# STM32-Nucleo-144_U575ZI-Q.net
KiCad netlist of a schematic drawn in Altium Designer
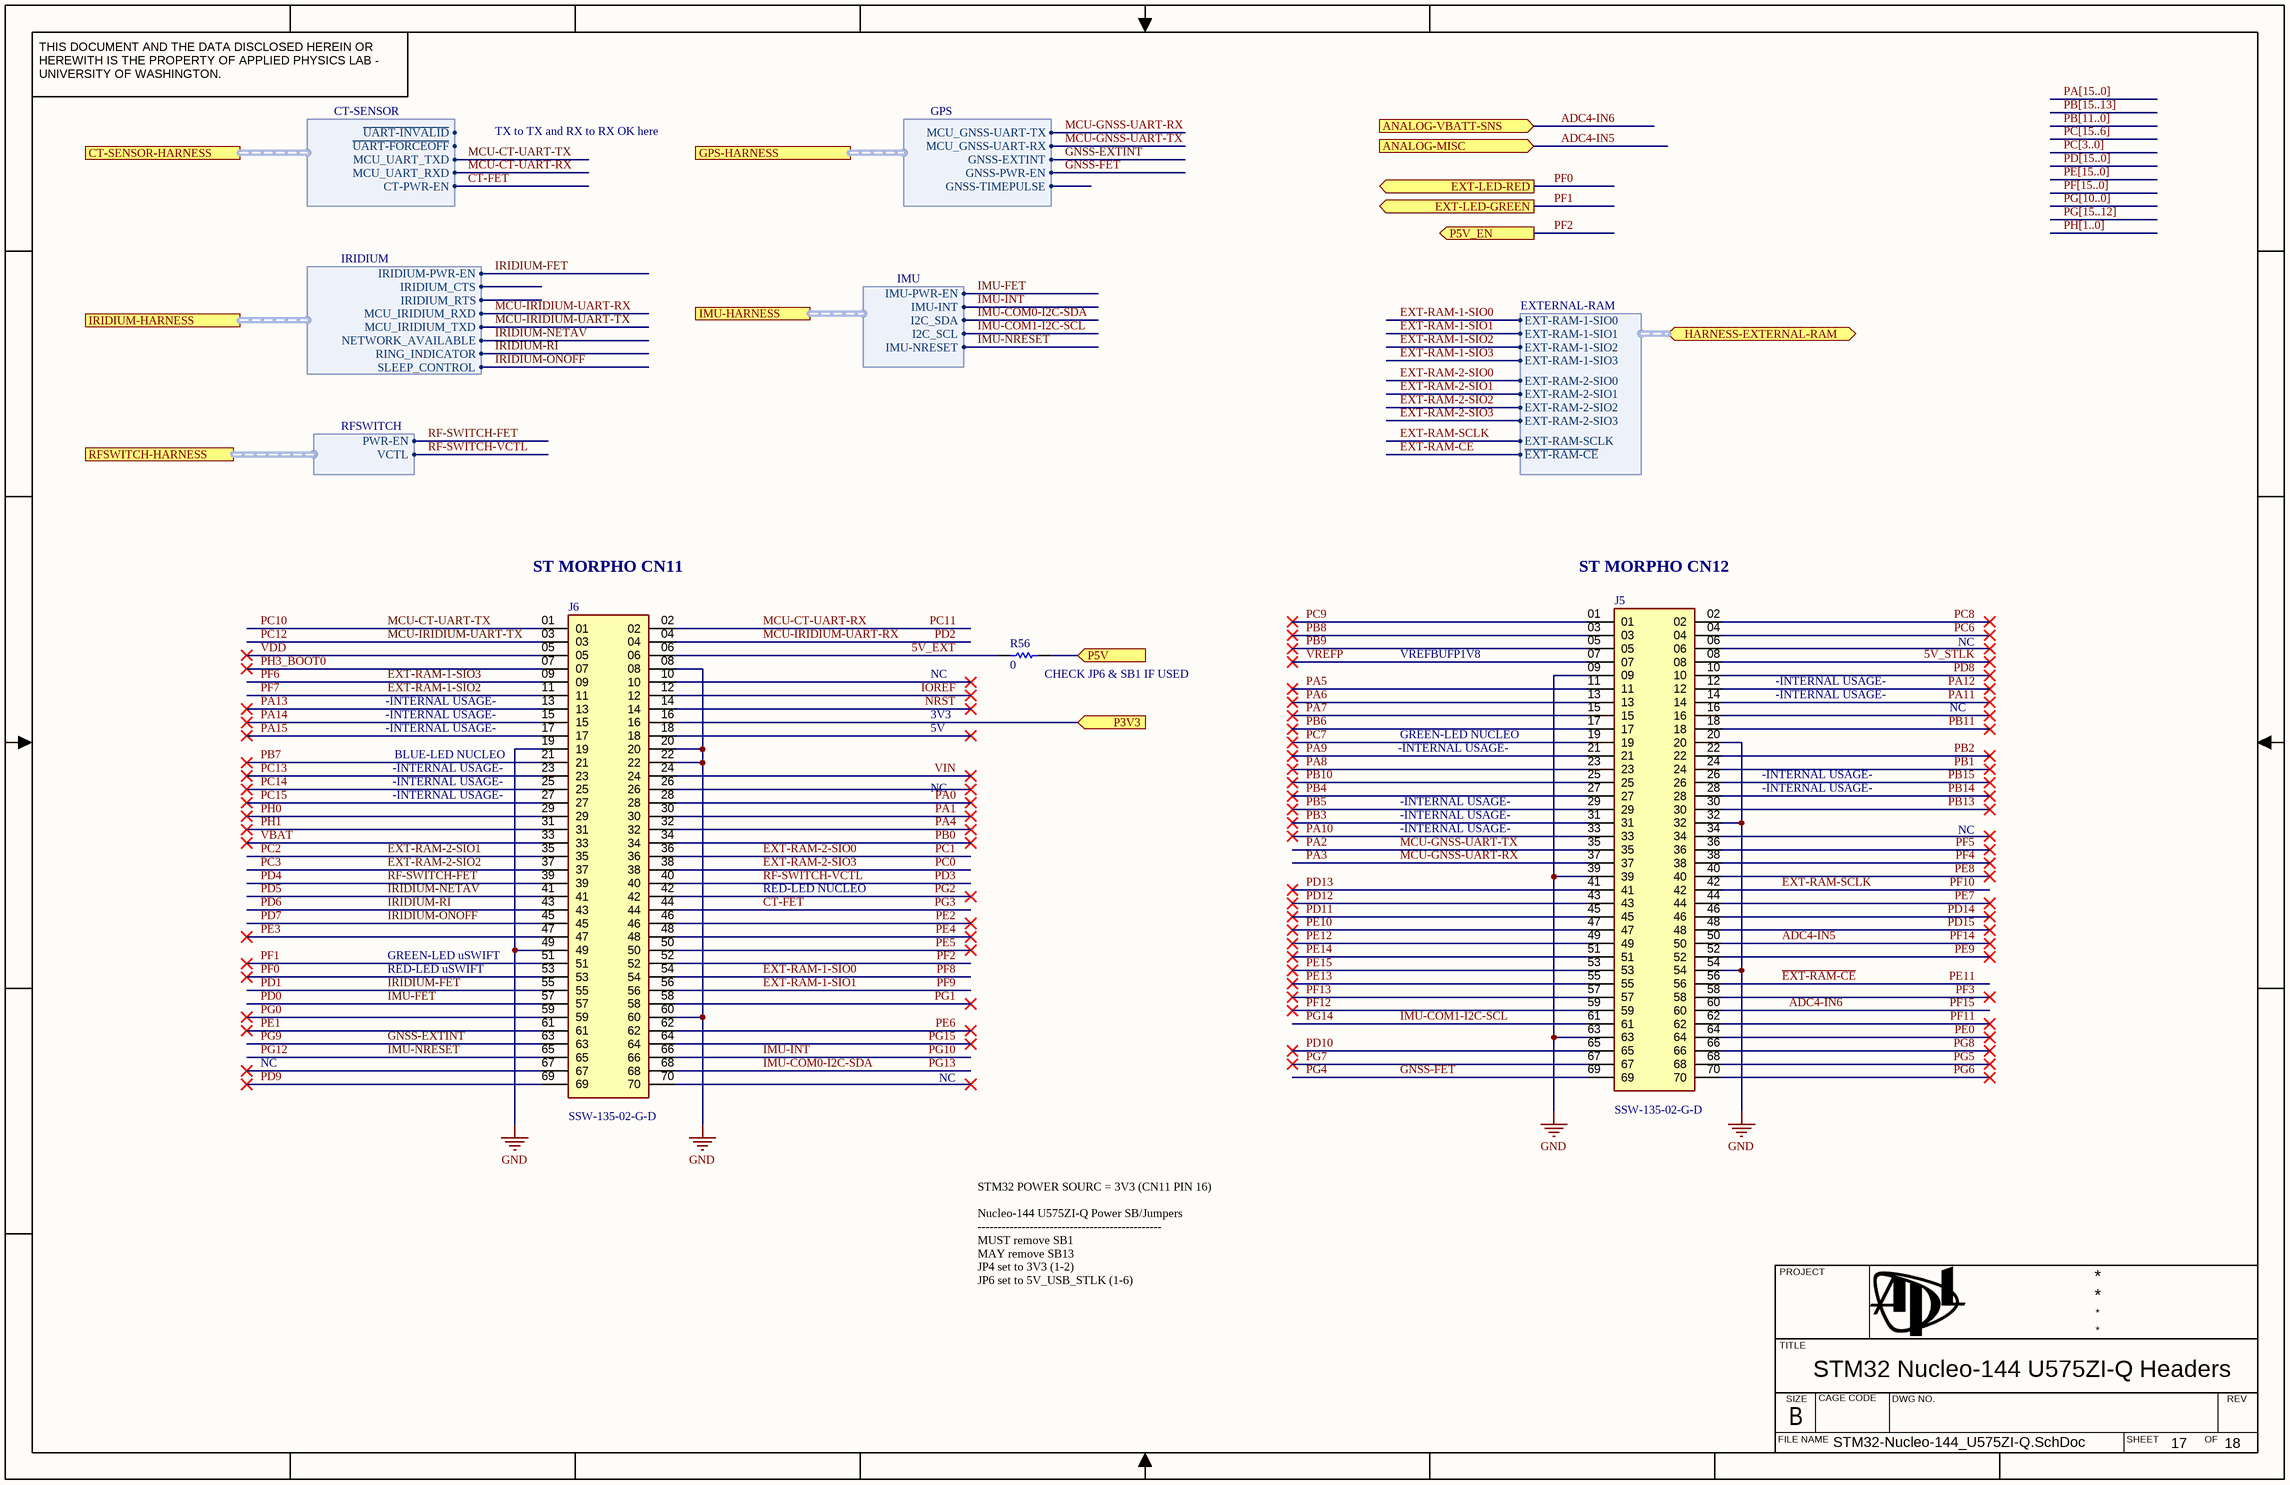
[diagram p0: STM32-Nucleo-144_U575ZI-Q.SchDoc]

(export (version "E")
  (design (tool "Eeschema 10.0.6"))
  (components
    (comp (ref "J5")
      (value "SSW-135-02-G-D")
      (footprint "SAMTEC_SSW-135-02-G-D")
      (description "Tiger Buy™ Socket Strip with PCB Tails, 0.100\" Pitch")
      (fields (field (name "MANUFACTURER") "Samtec"))
      (libsource (lib "Applied Physics Lab") (part "SSW-135-02-G-D"))
    )
    (comp (ref "J6")
      (value "SSW-135-02-G-D")
      (footprint "SAMTEC_SSW-135-02-G-D")
      (description "Tiger Buy™ Socket Strip with PCB Tails, 0.100\" Pitch")
      (fields (field (name "MANUFACTURER") "Samtec"))
      (libsource (lib "Applied Physics Lab") (part "SSW-135-02-G-D"))
    )
    (comp (ref "R56")
      (value "0")
      (footprint "RESC2013X50X35ML15T15")
      (description "Chip Resistor, 0 Ohm, +/- 1%, 125 mW, -55 to 155 degC, 0805 (2012 Metric)")
      (fields (field (name "TOLERANCE") "1%") (field (name "POWER") "125mW"))
      (libsource (lib "Applied Physics Lab") (part "RES-2"))
    )
  )
  (nets
    (net (code "7") (name "/5V_EXT") (class "Default")
      (node (ref "J6") (pin "06") (pinfunction "06_06") (pintype "passive"))
      (node (ref "R56") (pin "2") (pinfunction "2_2") (pintype "passive"))
    )
    (net (code "8") (name "/5V_STLK") (class "Default")
      (node (ref "J5") (pin "08") (pinfunction "08_08") (pintype "passive+no_connect"))
    )
    (net (code "9") (name "/IOREF") (class "Default")
      (node (ref "J6") (pin "12") (pinfunction "12_12") (pintype "passive+no_connect"))
    )
    (net (code "10") (name "/NRST") (class "Default")
      (node (ref "J6") (pin "14") (pinfunction "14_14") (pintype "passive+no_connect"))
    )
    (net (code "11") (name "/P3V3") (class "Default")
      (node (ref "J6") (pin "16") (pinfunction "16_16") (pintype "passive"))
    )
    (net (code "12") (name "/P5V") (class "Default")
      (node (ref "R56") (pin "1") (pinfunction "1_1") (pintype "passive"))
    )
    (net (code "13") (name "/PA0") (class "Default")
      (node (ref "J6") (pin "28") (pinfunction "28_28") (pintype "passive+no_connect"))
    )
    (net (code "14") (name "/PA1") (class "Default")
      (node (ref "J6") (pin "30") (pinfunction "30_30") (pintype "passive+no_connect"))
    )
    (net (code "15") (name "/PA2") (class "Default")
      (node (ref "J5") (pin "35") (pinfunction "35_35") (pintype "passive"))
    )
    (net (code "16") (name "/PA3") (class "Default")
      (node (ref "J5") (pin "37") (pinfunction "37_37") (pintype "passive"))
    )
    (net (code "17") (name "/PA4") (class "Default")
      (node (ref "J6") (pin "32") (pinfunction "32_32") (pintype "passive+no_connect"))
    )
    (net (code "18") (name "/PA5") (class "Default")
      (node (ref "J5") (pin "11") (pinfunction "11_11") (pintype "passive+no_connect"))
    )
    (net (code "19") (name "/PA6") (class "Default")
      (node (ref "J5") (pin "13") (pinfunction "13_13") (pintype "passive+no_connect"))
    )
    (net (code "20") (name "/PA7") (class "Default")
      (node (ref "J5") (pin "15") (pinfunction "15_15") (pintype "passive+no_connect"))
    )
    (net (code "21") (name "/PA8") (class "Default")
      (node (ref "J5") (pin "23") (pinfunction "23_23") (pintype "passive+no_connect"))
    )
    (net (code "22") (name "/PA9") (class "Default")
      (node (ref "J5") (pin "21") (pinfunction "21_21") (pintype "passive+no_connect"))
    )
    (net (code "23") (name "/PA10") (class "Default")
      (node (ref "J5") (pin "33") (pinfunction "33_33") (pintype "passive+no_connect"))
    )
    (net (code "24") (name "/PA11") (class "Default")
      (node (ref "J5") (pin "14") (pinfunction "14_14") (pintype "passive+no_connect"))
    )
    (net (code "25") (name "/PA12") (class "Default")
      (node (ref "J5") (pin "12") (pinfunction "12_12") (pintype "passive+no_connect"))
    )
    (net (code "26") (name "/PA13") (class "Default")
      (node (ref "J6") (pin "13") (pinfunction "13_13") (pintype "passive+no_connect"))
    )
    (net (code "27") (name "/PA14") (class "Default")
      (node (ref "J6") (pin "15") (pinfunction "15_15") (pintype "passive+no_connect"))
    )
    (net (code "28") (name "/PA15") (class "Default")
      (node (ref "J6") (pin "17") (pinfunction "17_17") (pintype "passive+no_connect"))
    )
    (net (code "30") (name "/PB0") (class "Default")
      (node (ref "J6") (pin "34") (pinfunction "34_34") (pintype "passive+no_connect"))
    )
    (net (code "31") (name "/PB1") (class "Default")
      (node (ref "J5") (pin "24") (pinfunction "24_24") (pintype "passive+no_connect"))
    )
    (net (code "32") (name "/PB2") (class "Default")
      (node (ref "J5") (pin "22") (pinfunction "22_22") (pintype "passive+no_connect"))
    )
    (net (code "33") (name "/PB3") (class "Default")
      (node (ref "J5") (pin "31") (pinfunction "31_31") (pintype "passive+no_connect"))
    )
    (net (code "34") (name "/PB4") (class "Default")
      (node (ref "J5") (pin "27") (pinfunction "27_27") (pintype "passive+no_connect"))
    )
    (net (code "35") (name "/PB5") (class "Default")
      (node (ref "J5") (pin "29") (pinfunction "29_29") (pintype "passive+no_connect"))
    )
    (net (code "36") (name "/PB6") (class "Default")
      (node (ref "J5") (pin "17") (pinfunction "17_17") (pintype "passive+no_connect"))
    )
    (net (code "37") (name "/PB7") (class "Default")
      (node (ref "J6") (pin "21") (pinfunction "21_21") (pintype "passive+no_connect"))
    )
    (net (code "38") (name "/PB8") (class "Default")
      (node (ref "J5") (pin "03") (pinfunction "03_03") (pintype "passive+no_connect"))
    )
    (net (code "39") (name "/PB9") (class "Default")
      (node (ref "J5") (pin "05") (pinfunction "05_05") (pintype "passive+no_connect"))
    )
    (net (code "40") (name "/PB10") (class "Default")
      (node (ref "J5") (pin "25") (pinfunction "25_25") (pintype "passive+no_connect"))
    )
    (net (code "41") (name "/PB11") (class "Default")
      (node (ref "J5") (pin "18") (pinfunction "18_18") (pintype "passive+no_connect"))
    )
    (net (code "42") (name "/PB13") (class "Default")
      (node (ref "J5") (pin "30") (pinfunction "30_30") (pintype "passive+no_connect"))
    )
    (net (code "43") (name "/PB14") (class "Default")
      (node (ref "J5") (pin "28") (pinfunction "28_28") (pintype "passive+no_connect"))
    )
    (net (code "44") (name "/PB15") (class "Default")
      (node (ref "J5") (pin "26") (pinfunction "26_26") (pintype "passive+no_connect"))
    )
    (net (code "47") (name "/PC0") (class "Default")
      (node (ref "J6") (pin "38") (pinfunction "38_38") (pintype "passive"))
    )
    (net (code "48") (name "/PC1") (class "Default")
      (node (ref "J6") (pin "36") (pinfunction "36_36") (pintype "passive"))
    )
    (net (code "49") (name "/PC2") (class "Default")
      (node (ref "J6") (pin "35") (pinfunction "35_35") (pintype "passive"))
    )
    (net (code "50") (name "/PC3") (class "Default")
      (node (ref "J6") (pin "37") (pinfunction "37_37") (pintype "passive"))
    )
    (net (code "51") (name "/PC6") (class "Default")
      (node (ref "J5") (pin "04") (pinfunction "04_04") (pintype "passive+no_connect"))
    )
    (net (code "52") (name "/PC7") (class "Default")
      (node (ref "J5") (pin "19") (pinfunction "19_19") (pintype "passive+no_connect"))
    )
    (net (code "53") (name "/PC8") (class "Default")
      (node (ref "J5") (pin "02") (pinfunction "02_02") (pintype "passive+no_connect"))
    )
    (net (code "54") (name "/PC9") (class "Default")
      (node (ref "J5") (pin "01") (pinfunction "01_01") (pintype "passive+no_connect"))
    )
    (net (code "55") (name "/PC10") (class "Default")
      (node (ref "J6") (pin "01") (pinfunction "01_01") (pintype "passive"))
    )
    (net (code "56") (name "/PC11") (class "Default")
      (node (ref "J6") (pin "02") (pinfunction "02_02") (pintype "passive"))
    )
    (net (code "57") (name "/PC12") (class "Default")
      (node (ref "J6") (pin "03") (pinfunction "03_03") (pintype "passive"))
    )
    (net (code "58") (name "/PC13") (class "Default")
      (node (ref "J6") (pin "23") (pinfunction "23_23") (pintype "passive+no_connect"))
    )
    (net (code "59") (name "/PC14") (class "Default")
      (node (ref "J6") (pin "25") (pinfunction "25_25") (pintype "passive+no_connect"))
    )
    (net (code "60") (name "/PC15") (class "Default")
      (node (ref "J6") (pin "27") (pinfunction "27_27") (pintype "passive+no_connect"))
    )
    (net (code "63") (name "/PD0") (class "Default")
      (node (ref "J6") (pin "57") (pinfunction "57_57") (pintype "passive"))
    )
    (net (code "64") (name "/PD1") (class "Default")
      (node (ref "J6") (pin "55") (pinfunction "55_55") (pintype "passive"))
    )
    (net (code "65") (name "/PD2") (class "Default")
      (node (ref "J6") (pin "04") (pinfunction "04_04") (pintype "passive"))
    )
    (net (code "66") (name "/PD3") (class "Default")
      (node (ref "J6") (pin "40") (pinfunction "40_40") (pintype "passive"))
    )
    (net (code "67") (name "/PD4") (class "Default")
      (node (ref "J6") (pin "39") (pinfunction "39_39") (pintype "passive"))
    )
    (net (code "68") (name "/PD5") (class "Default")
      (node (ref "J6") (pin "41") (pinfunction "41_41") (pintype "passive"))
    )
    (net (code "69") (name "/PD6") (class "Default")
      (node (ref "J6") (pin "43") (pinfunction "43_43") (pintype "passive"))
    )
    (net (code "70") (name "/PD7") (class "Default")
      (node (ref "J6") (pin "45") (pinfunction "45_45") (pintype "passive"))
    )
    (net (code "71") (name "/PD8") (class "Default")
      (node (ref "J5") (pin "10") (pinfunction "10_10") (pintype "passive+no_connect"))
    )
    (net (code "72") (name "/PD9") (class "Default")
      (node (ref "J6") (pin "69") (pinfunction "69_69") (pintype "passive+no_connect"))
    )
    (net (code "73") (name "/PD10") (class "Default")
      (node (ref "J5") (pin "65") (pinfunction "65_65") (pintype "passive+no_connect"))
    )
    (net (code "74") (name "/PD11") (class "Default")
      (node (ref "J5") (pin "45") (pinfunction "45_45") (pintype "passive+no_connect"))
    )
    (net (code "75") (name "/PD12") (class "Default")
      (node (ref "J5") (pin "43") (pinfunction "43_43") (pintype "passive+no_connect"))
    )
    (net (code "76") (name "/PD13") (class "Default")
      (node (ref "J5") (pin "41") (pinfunction "41_41") (pintype "passive+no_connect"))
    )
    (net (code "77") (name "/PD14") (class "Default")
      (node (ref "J5") (pin "46") (pinfunction "46_46") (pintype "passive+no_connect"))
    )
    (net (code "78") (name "/PD15") (class "Default")
      (node (ref "J5") (pin "48") (pinfunction "48_48") (pintype "passive+no_connect"))
    )
    (net (code "80") (name "/PE0") (class "Default")
      (node (ref "J5") (pin "64") (pinfunction "64_64") (pintype "passive+no_connect"))
    )
    (net (code "81") (name "/PE1") (class "Default")
      (node (ref "J6") (pin "61") (pinfunction "61_61") (pintype "passive+no_connect"))
    )
    (net (code "82") (name "/PE2") (class "Default")
      (node (ref "J6") (pin "46") (pinfunction "46_46") (pintype "passive+no_connect"))
    )
    (net (code "83") (name "/PE3") (class "Default")
      (node (ref "J6") (pin "47") (pinfunction "47_47") (pintype "passive+no_connect"))
    )
    (net (code "84") (name "/PE4") (class "Default")
      (node (ref "J6") (pin "48") (pinfunction "48_48") (pintype "passive+no_connect"))
    )
    (net (code "85") (name "/PE5") (class "Default")
      (node (ref "J6") (pin "50") (pinfunction "50_50") (pintype "passive+no_connect"))
    )
    (net (code "86") (name "/PE6") (class "Default")
      (node (ref "J6") (pin "62") (pinfunction "62_62") (pintype "passive+no_connect"))
    )
    (net (code "87") (name "/PE7") (class "Default")
      (node (ref "J5") (pin "44") (pinfunction "44_44") (pintype "passive+no_connect"))
    )
    (net (code "88") (name "/PE8") (class "Default")
      (node (ref "J5") (pin "40") (pinfunction "40_40") (pintype "passive+no_connect"))
    )
    (net (code "89") (name "/PE9") (class "Default")
      (node (ref "J5") (pin "52") (pinfunction "52_52") (pintype "passive+no_connect"))
    )
    (net (code "90") (name "/PE10") (class "Default")
      (node (ref "J5") (pin "47") (pinfunction "47_47") (pintype "passive+no_connect"))
    )
    (net (code "91") (name "/PE11") (class "Default")
      (node (ref "J5") (pin "56") (pinfunction "56_56") (pintype "passive"))
    )
    (net (code "92") (name "/PE12") (class "Default")
      (node (ref "J5") (pin "49") (pinfunction "49_49") (pintype "passive+no_connect"))
    )
    (net (code "93") (name "/PE13") (class "Default")
      (node (ref "J5") (pin "55") (pinfunction "55_55") (pintype "passive+no_connect"))
    )
    (net (code "94") (name "/PE14") (class "Default")
      (node (ref "J5") (pin "51") (pinfunction "51_51") (pintype "passive+no_connect"))
    )
    (net (code "95") (name "/PE15") (class "Default")
      (node (ref "J5") (pin "53") (pinfunction "53_53") (pintype "passive+no_connect"))
    )
    (net (code "97") (name "/PF0") (class "Default")
      (node (ref "J6") (pin "53") (pinfunction "53_53") (pintype "passive+no_connect"))
    )
    (net (code "98") (name "/PF1") (class "Default")
      (node (ref "J6") (pin "51") (pinfunction "51_51") (pintype "passive+no_connect"))
    )
    (net (code "99") (name "/PF2") (class "Default")
      (node (ref "J6") (pin "52") (pinfunction "52_52") (pintype "passive"))
    )
    (net (code "100") (name "/PF3") (class "Default")
      (node (ref "J5") (pin "58") (pinfunction "58_58") (pintype "passive+no_connect"))
    )
    (net (code "101") (name "/PF4") (class "Default")
      (node (ref "J5") (pin "38") (pinfunction "38_38") (pintype "passive+no_connect"))
    )
    (net (code "102") (name "/PF5") (class "Default")
      (node (ref "J5") (pin "36") (pinfunction "36_36") (pintype "passive+no_connect"))
    )
    (net (code "103") (name "/PF6") (class "Default")
      (node (ref "J6") (pin "09") (pinfunction "09_09") (pintype "passive"))
    )
    (net (code "104") (name "/PF7") (class "Default")
      (node (ref "J6") (pin "11") (pinfunction "11_11") (pintype "passive"))
    )
    (net (code "105") (name "/PF8") (class "Default")
      (node (ref "J6") (pin "54") (pinfunction "54_54") (pintype "passive"))
    )
    (net (code "106") (name "/PF9") (class "Default")
      (node (ref "J6") (pin "56") (pinfunction "56_56") (pintype "passive"))
    )
    (net (code "107") (name "/PF10") (class "Default")
      (node (ref "J5") (pin "42") (pinfunction "42_42") (pintype "passive"))
    )
    (net (code "108") (name "/PF11") (class "Default")
      (node (ref "J5") (pin "62") (pinfunction "62_62") (pintype "passive+no_connect"))
    )
    (net (code "109") (name "/PF12") (class "Default")
      (node (ref "J5") (pin "59") (pinfunction "59_59") (pintype "passive+no_connect"))
    )
    (net (code "110") (name "/PF13") (class "Default")
      (node (ref "J5") (pin "57") (pinfunction "57_57") (pintype "passive+no_connect"))
    )
    (net (code "111") (name "/PF14") (class "Default")
      (node (ref "J5") (pin "50") (pinfunction "50_50") (pintype "passive"))
    )
    (net (code "112") (name "/PF15") (class "Default")
      (node (ref "J5") (pin "60") (pinfunction "60_60") (pintype "passive"))
    )
    (net (code "114") (name "/PG0") (class "Default")
      (node (ref "J6") (pin "59") (pinfunction "59_59") (pintype "passive+no_connect"))
    )
    (net (code "115") (name "/PG1") (class "Default")
      (node (ref "J6") (pin "58") (pinfunction "58_58") (pintype "passive+no_connect"))
    )
    (net (code "116") (name "/PG2") (class "Default")
      (node (ref "J6") (pin "42") (pinfunction "42_42") (pintype "passive+no_connect"))
    )
    (net (code "117") (name "/PG3") (class "Default")
      (node (ref "J6") (pin "44") (pinfunction "44_44") (pintype "passive"))
    )
    (net (code "118") (name "/PG4") (class "Default")
      (node (ref "J5") (pin "69") (pinfunction "69_69") (pintype "passive"))
    )
    (net (code "119") (name "/PG5") (class "Default")
      (node (ref "J5") (pin "68") (pinfunction "68_68") (pintype "passive+no_connect"))
    )
    (net (code "120") (name "/PG6") (class "Default")
      (node (ref "J5") (pin "70") (pinfunction "70_70") (pintype "passive+no_connect"))
    )
    (net (code "121") (name "/PG7") (class "Default")
      (node (ref "J5") (pin "67") (pinfunction "67_67") (pintype "passive+no_connect"))
    )
    (net (code "122") (name "/PG8") (class "Default")
      (node (ref "J5") (pin "66") (pinfunction "66_66") (pintype "passive+no_connect"))
    )
    (net (code "123") (name "/PG9") (class "Default")
      (node (ref "J6") (pin "63") (pinfunction "63_63") (pintype "passive"))
    )
    (net (code "124") (name "/PG10") (class "Default")
      (node (ref "J6") (pin "66") (pinfunction "66_66") (pintype "passive"))
    )
    (net (code "125") (name "/PG12") (class "Default")
      (node (ref "J6") (pin "65") (pinfunction "65_65") (pintype "passive"))
    )
    (net (code "126") (name "/PG13") (class "Default")
      (node (ref "J6") (pin "68") (pinfunction "68_68") (pintype "passive"))
    )
    (net (code "127") (name "/PG14") (class "Default")
      (node (ref "J5") (pin "61") (pinfunction "61_61") (pintype "passive"))
    )
    (net (code "128") (name "/PG15") (class "Default")
      (node (ref "J6") (pin "64") (pinfunction "64_64") (pintype "passive+no_connect"))
    )
    (net (code "131") (name "/PH0") (class "Default")
      (node (ref "J6") (pin "29") (pinfunction "29_29") (pintype "passive+no_connect"))
    )
    (net (code "132") (name "/PH1") (class "Default")
      (node (ref "J6") (pin "31") (pinfunction "31_31") (pintype "passive+no_connect"))
    )
    (net (code "133") (name "/PH3_BOOT0") (class "Default")
      (node (ref "J6") (pin "07") (pinfunction "07_07") (pintype "passive+no_connect"))
    )
    (net (code "135") (name "/VBAT") (class "Default")
      (node (ref "J6") (pin "33") (pinfunction "33_33") (pintype "passive+no_connect"))
    )
    (net (code "136") (name "/VDD") (class "Default")
      (node (ref "J6") (pin "05") (pinfunction "05_05") (pintype "passive+no_connect"))
    )
    (net (code "137") (name "/VIN") (class "Default")
      (node (ref "J6") (pin "24") (pinfunction "24_24") (pintype "passive+no_connect"))
    )
    (net (code "138") (name "/VREFP") (class "Default")
      (node (ref "J5") (pin "07") (pinfunction "07_07") (pintype "passive+no_connect"))
    )
    (net (code "145") (name "GND") (class "Default")
      (node (ref "J5") (pin "09") (pinfunction "09_09") (pintype "passive"))
      (node (ref "J5") (pin "20") (pinfunction "20_20") (pintype "passive"))
      (node (ref "J5") (pin "32") (pinfunction "32_32") (pintype "passive"))
      (node (ref "J5") (pin "39") (pinfunction "39_39") (pintype "passive"))
      (node (ref "J5") (pin "54") (pinfunction "54_54") (pintype "passive"))
      (node (ref "J5") (pin "63") (pinfunction "63_63") (pintype "passive"))
      (node (ref "J6") (pin "08") (pinfunction "08_08") (pintype "passive"))
      (node (ref "J6") (pin "19") (pinfunction "19_19") (pintype "passive"))
      (node (ref "J6") (pin "20") (pinfunction "20_20") (pintype "passive"))
      (node (ref "J6") (pin "22") (pinfunction "22_22") (pintype "passive"))
      (node (ref "J6") (pin "49") (pinfunction "49_49") (pintype "passive"))
      (node (ref "J6") (pin "60") (pinfunction "60_60") (pintype "passive"))
    )
    (net (code "146") (name "unconnected-(J5-Pad06)") (class "Default")
      (node (ref "J5") (pin "06") (pinfunction "06_06") (pintype "passive+no_connect"))
    )
    (net (code "147") (name "unconnected-(J5-Pad16)") (class "Default")
      (node (ref "J5") (pin "16") (pinfunction "16_16") (pintype "passive+no_connect"))
    )
    (net (code "148") (name "unconnected-(J5-Pad34)") (class "Default")
      (node (ref "J5") (pin "34") (pinfunction "34_34") (pintype "passive+no_connect"))
    )
    (net (code "149") (name "unconnected-(J6-Pad10)") (class "Default")
      (node (ref "J6") (pin "10") (pinfunction "10_10") (pintype "passive+no_connect"))
    )
    (net (code "150") (name "unconnected-(J6-Pad18)") (class "Default")
      (node (ref "J6") (pin "18") (pinfunction "18_18") (pintype "passive+no_connect"))
    )
    (net (code "151") (name "unconnected-(J6-Pad26)") (class "Default")
      (node (ref "J6") (pin "26") (pinfunction "26_26") (pintype "passive+no_connect"))
    )
    (net (code "152") (name "unconnected-(J6-Pad67)") (class "Default")
      (node (ref "J6") (pin "67") (pinfunction "67_67") (pintype "passive+no_connect"))
    )
    (net (code "153") (name "unconnected-(J6-Pad70)") (class "Default")
      (node (ref "J6") (pin "70") (pinfunction "70_70") (pintype "passive+no_connect"))
    )
  )
)
